# Memory.net
KiCad netlist of a schematic drawn in Altium Designer
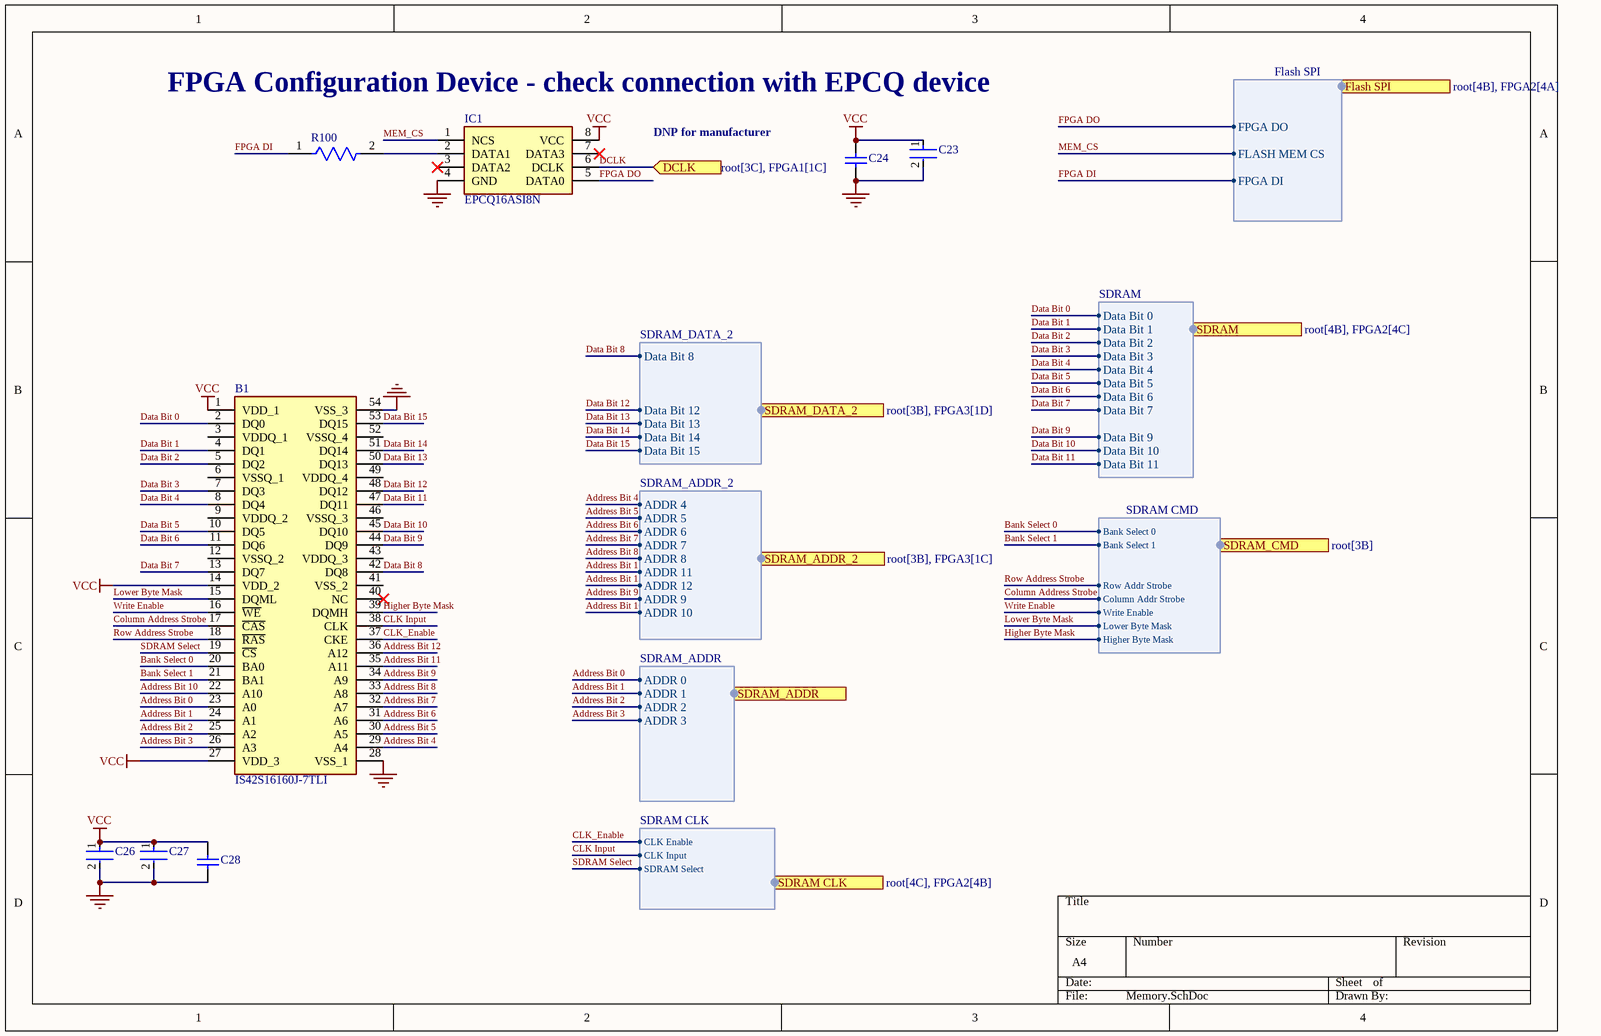
[diagram p0: Memory.SchDoc]

(export (version "E")
  (design (tool "Eeschema 10.0.6"))
  (components
    (comp (ref "B1")
      (value "IS42S16160J-7TLI")
      (footprint "SOP80P1176X120-54N")
      (description "DRAM 256M, 3.3V, SDRAM 16Mx16 143MHz")
      (fields (field (name "MOUSER PART NUMBER") "870-IS42S16160J-7TLI"))
      (libsource (lib "University of British Columbia") (part "IS42S16160J-7TLI"))
    )
    (comp (ref "C23")
      (value "CC0402KRX7R7BB104")
      (footprint "FP-CC0402-MFG")
      (description "CAP CER 0.1UF 16V X7R 0402")
      (fields (field (name "MANUFACTURER") "YAGEO") (field (name "TOLERANCE") "0.1"))
      (libsource (lib "Altium Content Vault") (part "11868f565c42a9108669ba33697ecf6"))
    )
    (comp (ref "C24")
      (value "C0603C105K9PACTU")
      (footprint "CAPC1608X90X35LL15T15")
      (fields (field (name "MANUFACTURER") "Kemet"))
      (libsource (lib "Altium Content Vault") (part "CAP"))
    )
    (comp (ref "C26")
      (value "CC0603KRX7R9BB104")
      (footprint "FP-CC0603-DA-MFG")
      (description "CAP CER 0.1UF 50V X7R 0603")
      (fields (field (name "MANUFACTURER") "YAGEO") (field (name "VOLTAGE") "50 V"))
      (libsource (lib "Altium Content Vault") (part "11868f565c42a9108669ba33697ecf6"))
    )
    (comp (ref "C27")
      (value "CL21A475KAQNNNE")
      (footprint "FP-CL21-IPC_A")
      (description "CL21 Series 0805 4.7uF 25V ±10% Tolerance X5R Multilayer Ceramic Chip Capacitor")
      (fields (field (name "TOLERANCE") "10%"))
      (libsource (lib "Altium Content Vault") (part "b4654b650e69147ec39a6b967a45e02"))
    )
    (comp (ref "C28")
      (value "C0603C105K9PACTU")
      (footprint "CAPC1608X90X35LL15T15")
      (fields (field (name "MANUFACTURER") "Kemet"))
      (libsource (lib "Altium Content Vault") (part "CAP"))
    )
    (comp (ref "IC1")
      (value "EPCQ16ASI8N")
      (footprint "SOP80P1176X120-54N:SOIC127P600X175-8N")
      (description "Integrated Circuit")
      (fields (field (name "MOUSER PART NUMBER") "989-EPCQ16ASI8N"))
      (libsource (lib "*") (part "EPCQ16ASI8N"))
    )
    (comp (ref "R100")
      (value "RC0402JR-0722RL")
      (footprint "FP-RC0402-0_4-IPC_B")
      (description "RES SMD 22 OHM 5% 1/16W 0402")
      (fields (field (name "TOLERANCE") "5%"))
      (libsource (lib "Altium Content Vault") (part "1029c3af85768c4190bb7ad29bc67b5"))
    )
  )
  (nets
    (net (code "9") (name "/Address Bit 0") (class "Default")
      (node (ref "B1") (pin "23") (pinfunction "A0_23") (pintype "passive"))
    )
    (net (code "10") (name "/Address Bit 1") (class "Default")
      (node (ref "B1") (pin "24") (pinfunction "A1_24") (pintype "passive"))
    )
    (net (code "11") (name "/Address Bit 2") (class "Default")
      (node (ref "B1") (pin "25") (pinfunction "A2_25") (pintype "passive"))
    )
    (net (code "12") (name "/Address Bit 3") (class "Default")
      (node (ref "B1") (pin "26") (pinfunction "A3_26") (pintype "passive"))
    )
    (net (code "13") (name "/Address Bit 4") (class "Default")
      (node (ref "B1") (pin "29") (pinfunction "A4_29") (pintype "passive"))
    )
    (net (code "14") (name "/Address Bit 5") (class "Default")
      (node (ref "B1") (pin "30") (pinfunction "A5_30") (pintype "passive"))
    )
    (net (code "15") (name "/Address Bit 6") (class "Default")
      (node (ref "B1") (pin "31") (pinfunction "A6_31") (pintype "passive"))
    )
    (net (code "16") (name "/Address Bit 7") (class "Default")
      (node (ref "B1") (pin "32") (pinfunction "A7_32") (pintype "passive"))
    )
    (net (code "17") (name "/Address Bit 8") (class "Default")
      (node (ref "B1") (pin "33") (pinfunction "A8_33") (pintype "passive"))
    )
    (net (code "18") (name "/Address Bit 9") (class "Default")
      (node (ref "B1") (pin "34") (pinfunction "A9_34") (pintype "passive"))
    )
    (net (code "19") (name "/Address Bit 10") (class "Default")
      (node (ref "B1") (pin "22") (pinfunction "A10_22") (pintype "passive"))
    )
    (net (code "20") (name "/Address Bit 11") (class "Default")
      (node (ref "B1") (pin "35") (pinfunction "A11_35") (pintype "passive"))
    )
    (net (code "21") (name "/Address Bit 12") (class "Default")
      (node (ref "B1") (pin "36") (pinfunction "A12_36") (pintype "passive"))
    )
    (net (code "22") (name "/Bank Select 0") (class "Default")
      (node (ref "B1") (pin "20") (pinfunction "BA0_20") (pintype "passive"))
    )
    (net (code "23") (name "/Bank Select 1") (class "Default")
      (node (ref "B1") (pin "21") (pinfunction "BA1_21") (pintype "passive"))
    )
    (net (code "24") (name "/CLK Input") (class "Default")
      (node (ref "B1") (pin "38") (pinfunction "CLK_38") (pintype "passive"))
    )
    (net (code "25") (name "/CLK_Enable") (class "Default")
      (node (ref "B1") (pin "37") (pinfunction "CKE_37") (pintype "passive"))
    )
    (net (code "26") (name "/Column Address Strobe") (class "Default")
      (node (ref "B1") (pin "17") (pinfunction "~{CAS}_17") (pintype "passive"))
    )
    (net (code "27") (name "/DCLK") (class "Default")
      (node (ref "IC1") (pin "6") (pinfunction "DCLK_6") (pintype "passive"))
    )
    (net (code "28") (name "/Data Bit 0") (class "Default")
      (node (ref "B1") (pin "2") (pinfunction "DQ0_2") (pintype "passive"))
    )
    (net (code "29") (name "/Data Bit 1") (class "Default")
      (node (ref "B1") (pin "4") (pinfunction "DQ1_4") (pintype "passive"))
    )
    (net (code "30") (name "/Data Bit 2") (class "Default")
      (node (ref "B1") (pin "5") (pinfunction "DQ2_5") (pintype "passive"))
    )
    (net (code "31") (name "/Data Bit 3") (class "Default")
      (node (ref "B1") (pin "7") (pinfunction "DQ3_7") (pintype "passive"))
    )
    (net (code "32") (name "/Data Bit 4") (class "Default")
      (node (ref "B1") (pin "8") (pinfunction "DQ4_8") (pintype "passive"))
    )
    (net (code "33") (name "/Data Bit 5") (class "Default")
      (node (ref "B1") (pin "10") (pinfunction "DQ5_10") (pintype "passive"))
    )
    (net (code "34") (name "/Data Bit 6") (class "Default")
      (node (ref "B1") (pin "11") (pinfunction "DQ6_11") (pintype "passive"))
    )
    (net (code "35") (name "/Data Bit 7") (class "Default")
      (node (ref "B1") (pin "13") (pinfunction "DQ7_13") (pintype "passive"))
    )
    (net (code "36") (name "/Data Bit 8") (class "Default")
      (node (ref "B1") (pin "42") (pinfunction "DQ8_42") (pintype "passive"))
    )
    (net (code "37") (name "/Data Bit 9") (class "Default")
      (node (ref "B1") (pin "44") (pinfunction "DQ9_44") (pintype "passive"))
    )
    (net (code "38") (name "/Data Bit 10") (class "Default")
      (node (ref "B1") (pin "45") (pinfunction "DQ10_45") (pintype "passive"))
    )
    (net (code "39") (name "/Data Bit 11") (class "Default")
      (node (ref "B1") (pin "47") (pinfunction "DQ11_47") (pintype "passive"))
    )
    (net (code "40") (name "/Data Bit 12") (class "Default")
      (node (ref "B1") (pin "48") (pinfunction "DQ12_48") (pintype "passive"))
    )
    (net (code "41") (name "/Data Bit 13") (class "Default")
      (node (ref "B1") (pin "50") (pinfunction "DQ13_50") (pintype "passive"))
    )
    (net (code "42") (name "/Data Bit 14") (class "Default")
      (node (ref "B1") (pin "51") (pinfunction "DQ14_51") (pintype "passive"))
    )
    (net (code "43") (name "/Data Bit 15") (class "Default")
      (node (ref "B1") (pin "53") (pinfunction "DQ15_53") (pintype "passive"))
    )
    (net (code "44") (name "/FPGA DI") (class "Default")
      (node (ref "R100") (pin "1") (pinfunction "1_1") (pintype "passive"))
    )
    (net (code "45") (name "/FPGA DO") (class "Default")
      (node (ref "IC1") (pin "5") (pinfunction "DATA0_5") (pintype "passive"))
    )
    (net (code "46") (name "/Higher Byte Mask") (class "Default")
      (node (ref "B1") (pin "39") (pinfunction "DQMH_39") (pintype "passive"))
    )
    (net (code "47") (name "/Lower Byte Mask") (class "Default")
      (node (ref "B1") (pin "15") (pinfunction "DQML_15") (pintype "passive"))
    )
    (net (code "48") (name "/MEM_CS") (class "Default")
      (node (ref "IC1") (pin "1") (pinfunction "NCS_1") (pintype "passive"))
    )
    (net (code "49") (name "/Row Address Strobe") (class "Default")
      (node (ref "B1") (pin "18") (pinfunction "~{RAS}_18") (pintype "passive"))
    )
    (net (code "50") (name "/SDRAM Select") (class "Default")
      (node (ref "B1") (pin "19") (pinfunction "~{CS}_19") (pintype "passive"))
    )
    (net (code "51") (name "/Write Enable") (class "Default")
      (node (ref "B1") (pin "16") (pinfunction "~{WE}_16") (pintype "passive"))
    )
    (net (code "59") (name "GND") (class "Default")
      (node (ref "B1") (pin "28") (pinfunction "VSS_1_28") (pintype "passive"))
      (node (ref "B1") (pin "54") (pinfunction "VSS_3_54") (pintype "passive"))
      (node (ref "C23") (pin "2") (pinfunction "2_2") (pintype "passive"))
      (node (ref "C24") (pin "1") (pinfunction "1_1") (pintype "passive"))
      (node (ref "C26") (pin "2") (pinfunction "2_2") (pintype "passive"))
      (node (ref "C27") (pin "2") (pinfunction "2_2") (pintype "passive"))
      (node (ref "C28") (pin "1") (pinfunction "1_1") (pintype "passive"))
      (node (ref "IC1") (pin "4") (pinfunction "GND_4") (pintype "passive"))
    )
    (net (code "60") (name "Net-(IC1-DATA1)") (class "Default")
      (node (ref "IC1") (pin "2") (pinfunction "DATA1_2") (pintype "passive"))
      (node (ref "R100") (pin "2") (pinfunction "2_2") (pintype "passive"))
    )
    (net (code "61") (name "VCC") (class "Default")
      (node (ref "B1") (pin "1") (pinfunction "VDD_1_1") (pintype "passive"))
      (node (ref "B1") (pin "14") (pinfunction "VDD_2_14") (pintype "passive"))
      (node (ref "B1") (pin "27") (pinfunction "VDD_3_27") (pintype "passive"))
      (node (ref "C23") (pin "1") (pinfunction "1_1") (pintype "passive"))
      (node (ref "C24") (pin "2") (pinfunction "2_2") (pintype "passive"))
      (node (ref "C26") (pin "1") (pinfunction "1_1") (pintype "passive"))
      (node (ref "C27") (pin "1") (pinfunction "1_1") (pintype "passive"))
      (node (ref "C28") (pin "2") (pinfunction "2_2") (pintype "passive"))
      (node (ref "IC1") (pin "8") (pinfunction "VCC_8") (pintype "passive"))
    )
    (net (code "62") (name "unconnected-(B1-NC-Pad40)") (class "Default")
      (node (ref "B1") (pin "40") (pinfunction "NC_40") (pintype "passive+no_connect"))
    )
    (net (code "63") (name "unconnected-(B1-VDDQ_1-Pad3)") (class "Default")
      (node (ref "B1") (pin "3") (pinfunction "VDDQ_1_3") (pintype "passive"))
    )
    (net (code "64") (name "unconnected-(B1-VDDQ_2-Pad9)") (class "Default")
      (node (ref "B1") (pin "9") (pinfunction "VDDQ_2_9") (pintype "passive"))
    )
    (net (code "65") (name "unconnected-(B1-VDDQ_3-Pad43)") (class "Default")
      (node (ref "B1") (pin "43") (pinfunction "VDDQ_3_43") (pintype "passive"))
    )
    (net (code "66") (name "unconnected-(B1-VDDQ_4-Pad49)") (class "Default")
      (node (ref "B1") (pin "49") (pinfunction "VDDQ_4_49") (pintype "passive"))
    )
    (net (code "67") (name "unconnected-(B1-VSSQ_1-Pad6)") (class "Default")
      (node (ref "B1") (pin "6") (pinfunction "VSSQ_1_6") (pintype "passive"))
    )
    (net (code "68") (name "unconnected-(B1-VSSQ_2-Pad12)") (class "Default")
      (node (ref "B1") (pin "12") (pinfunction "VSSQ_2_12") (pintype "passive"))
    )
    (net (code "69") (name "unconnected-(B1-VSSQ_3-Pad46)") (class "Default")
      (node (ref "B1") (pin "46") (pinfunction "VSSQ_3_46") (pintype "passive"))
    )
    (net (code "70") (name "unconnected-(B1-VSSQ_4-Pad52)") (class "Default")
      (node (ref "B1") (pin "52") (pinfunction "VSSQ_4_52") (pintype "passive"))
    )
    (net (code "71") (name "unconnected-(B1-VSS_2-Pad41)") (class "Default")
      (node (ref "B1") (pin "41") (pinfunction "VSS_2_41") (pintype "passive"))
    )
    (net (code "72") (name "unconnected-(IC1-DATA2-Pad3)") (class "Default")
      (node (ref "IC1") (pin "3") (pinfunction "DATA2_3") (pintype "passive+no_connect"))
    )
    (net (code "73") (name "unconnected-(IC1-DATA3-Pad7)") (class "Default")
      (node (ref "IC1") (pin "7") (pinfunction "DATA3_7") (pintype "passive+no_connect"))
    )
  )
)
